# robotarium-1.net
KiCad netlist of a schematic drawn in EAGLE
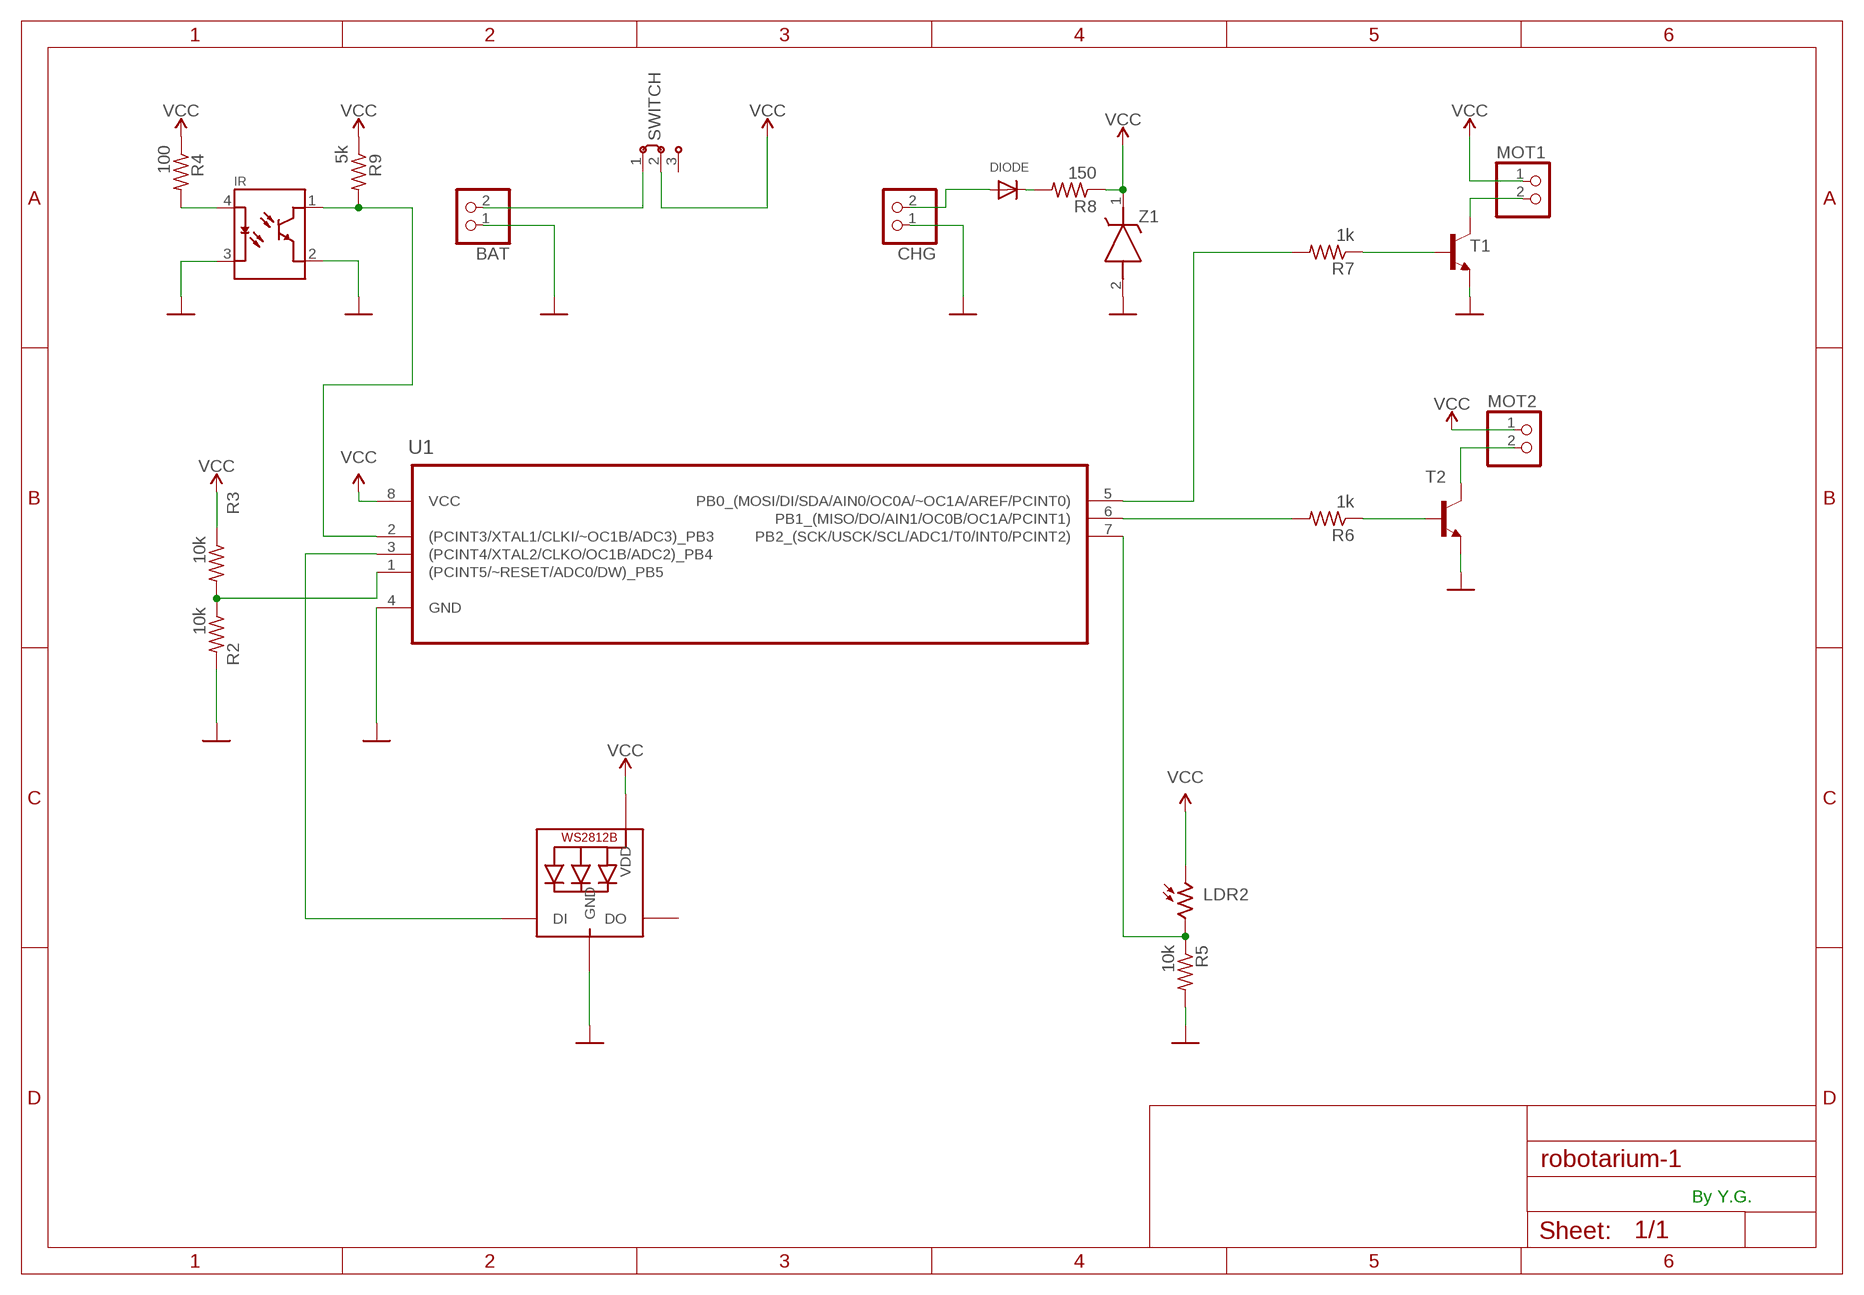
[diagram p0: schematic, sheet 1]

(export (version "E")
  (design (tool "Eeschema 10.0.6"))
  (components
    (comp (ref "BAT")
      (value "PINHD-1X2")
      (footprint "eagle-import:1X02")
      (libsource (lib "eagle-import") (part "PINHD-1X2"))
    )
    (comp (ref "CHG")
      (value "PINHD-1X2")
      (footprint "eagle-import:1X02")
      (libsource (lib "eagle-import") (part "PINHD-1X2"))
    )
    (comp (ref "DIODE")
      (value "DIODEDO-1N4148")
      (footprint "eagle-import:DO-1N4148")
      (libsource (lib "eagle-import") (part "DIODEDO-1N4148"))
    )
    (comp (ref "IR")
      (value "TCRT5000L")
      (footprint "eagle-import:XDCR_TCRT5000L")
      (fields (field (name "MF") "Vishay"))
      (libsource (lib "eagle-import") (part "TCRT5000L"))
    )
    (comp (ref "LDR2")
      (value "A1050_14")
      (footprint "eagle-import:T0-46-A10XX")
      (libsource (lib "eagle-import") (part "A1050_14"))
    )
    (comp (ref "LED2")
      (value "WS2812B5050")
      (footprint "eagle-import:WS2812B")
      (fields (field (name "MF") "SparkFun Electronics") (field (name "MP") "WS2812B"))
      (libsource (lib "eagle-import") (part "WS2812B5050"))
    )
    (comp (ref "MOT1")
      (value "PINHD-1X2")
      (footprint "eagle-import:1X02")
      (libsource (lib "eagle-import") (part "PINHD-1X2"))
    )
    (comp (ref "MOT2")
      (value "PINHD-1X2")
      (footprint "eagle-import:1X02")
      (libsource (lib "eagle-import") (part "PINHD-1X2"))
    )
    (comp (ref "R2")
      (value "10k")
      (footprint "eagle-import:0207_10")
      (libsource (lib "eagle-import") (part "R-US_0207/10"))
    )
    (comp (ref "R3")
      (value "10k")
      (footprint "eagle-import:0207_10")
      (libsource (lib "eagle-import") (part "R-US_0207/10"))
    )
    (comp (ref "R4")
      (value "100")
      (footprint "eagle-import:0207_10")
      (libsource (lib "eagle-import") (part "R-US_0207/10"))
    )
    (comp (ref "R5")
      (value "10k")
      (footprint "eagle-import:0207_10")
      (libsource (lib "eagle-import") (part "R-US_0207/10"))
    )
    (comp (ref "R6")
      (value "1k")
      (footprint "eagle-import:0207_10")
      (libsource (lib "eagle-import") (part "R-US_0207/10"))
    )
    (comp (ref "R7")
      (value "1k")
      (footprint "eagle-import:0207_10")
      (libsource (lib "eagle-import") (part "R-US_0207/10"))
    )
    (comp (ref "R8")
      (value "150")
      (footprint "eagle-import:0207_10")
      (libsource (lib "eagle-import") (part "R-US_0207/10"))
    )
    (comp (ref "R9")
      (value "5k")
      (footprint "eagle-import:0207_10")
      (libsource (lib "eagle-import") (part "R-US_0207/10"))
    )
    (comp (ref "SWITCH")
      (value "J2X2MM")
      (footprint "eagle-import:04C")
      (libsource (lib "eagle-import") (part "J2X2MM"))
    )
    (comp (ref "T1")
      (value "2N3904")
      (footprint "eagle-import:TO92")
      (libsource (lib "eagle-import") (part "2N3904"))
    )
    (comp (ref "T2")
      (value "2N3904")
      (footprint "eagle-import:TO92")
      (libsource (lib "eagle-import") (part "2N3904"))
    )
    (comp (ref "U1")
      (value "ATTINY85-20PU")
      (footprint "eagle-import:DIP254P762X533-8")
      (fields (field (name "MF") "Microchip"))
      (libsource (lib "eagle-import") (part "ATTINY85-20PU"))
    )
    (comp (ref "Z1")
      (value "BZX55C10")
      (footprint "eagle-import:DIOAD950W60L350D150")
      (fields
        (field (name "DIGI-KEY_PART_NUMBER") "BZX55C10-GICT-ND")
        (field (name "MF") "Vishay Semiconductor")
        (field (name "MP") "BZX55C10-TR")
      )
      (libsource (lib "eagle-import") (part "BZX55C10"))
    )
  )
  (nets
    (net (code "1") (name "GND") (class "Default")
      (node (ref "BAT") (pin "1") (pinfunction "1_1") (pintype "passive"))
      (node (ref "CHG") (pin "1") (pinfunction "1_1") (pintype "passive"))
      (node (ref "IR") (pin "2") (pinfunction "E_2") (pintype "passive"))
      (node (ref "IR") (pin "3") (pinfunction "C_3") (pintype "passive"))
      (node (ref "LED2") (pin "3-GND") (pinfunction "GND_3-GND") (pintype "power_in"))
      (node (ref "R2") (pin "2") (pinfunction "2_2") (pintype "passive"))
      (node (ref "R5") (pin "2") (pinfunction "2_2") (pintype "passive"))
      (node (ref "T1") (pin "3") (pinfunction "E_3") (pintype "passive"))
      (node (ref "T2") (pin "3") (pinfunction "E_3") (pintype "passive"))
      (node (ref "U1") (pin "4") (pinfunction "GND_4") (pintype "passive"))
      (node (ref "Z1") (pin "2") (pinfunction "A_2") (pintype "bidirectional"))
    )
    (net (code "2") (name "Net-(BAT-Pad2)") (class "Default")
      (node (ref "BAT") (pin "2") (pinfunction "2_2") (pintype "passive"))
      (node (ref "SWITCH") (pin "1") (pinfunction "1_1") (pintype "passive"))
    )
    (net (code "3") (name "Net-(CHG-Pad2)") (class "Default")
      (node (ref "CHG") (pin "2") (pinfunction "2_2") (pintype "passive"))
      (node (ref "DIODE") (pin "A") (pinfunction "A_A") (pintype "passive"))
    )
    (net (code "4") (name "Net-(DIODE-PadC)") (class "Default")
      (node (ref "DIODE") (pin "C") (pinfunction "C_C") (pintype "passive"))
      (node (ref "R8") (pin "2") (pinfunction "2_2") (pintype "passive"))
    )
    (net (code "5") (name "Net-(IR-A)") (class "Default")
      (node (ref "IR") (pin "4") (pinfunction "A_4") (pintype "passive"))
      (node (ref "R4") (pin "2") (pinfunction "2_2") (pintype "passive"))
    )
    (net (code "6") (name "Net-(IR-CO)") (class "Default")
      (node (ref "IR") (pin "1") (pinfunction "CO_1") (pintype "passive"))
      (node (ref "R9") (pin "2") (pinfunction "2_2") (pintype "passive"))
      (node (ref "U1") (pin "2") (pinfunction "(PCINT3/XTAL1/CLKI/~{OC1B/ADC3})_PB3_2") (pintype "bidirectional"))
    )
    (net (code "7") (name "Net-(LED2-DI)") (class "Default")
      (node (ref "LED2") (pin "4-DIN") (pinfunction "DI_4-DIN") (pintype "input"))
      (node (ref "U1") (pin "3") (pinfunction "(PCINT4/XTAL2/CLKO/OC1B/ADC2)_PB4_3") (pintype "bidirectional"))
    )
    (net (code "8") (name "Net-(T1-B)") (class "Default")
      (node (ref "R7") (pin "1") (pinfunction "1_1") (pintype "passive"))
      (node (ref "T1") (pin "2") (pinfunction "B_2") (pintype "passive"))
    )
    (net (code "9") (name "Net-(T1-C)") (class "Default")
      (node (ref "MOT1") (pin "2") (pinfunction "2_2") (pintype "passive"))
      (node (ref "T1") (pin "1") (pinfunction "C_1") (pintype "passive"))
    )
    (net (code "10") (name "Net-(T2-B)") (class "Default")
      (node (ref "R6") (pin "1") (pinfunction "1_1") (pintype "passive"))
      (node (ref "T2") (pin "2") (pinfunction "B_2") (pintype "passive"))
    )
    (net (code "11") (name "Net-(T2-C)") (class "Default")
      (node (ref "MOT2") (pin "2") (pinfunction "2_2") (pintype "passive"))
      (node (ref "T2") (pin "1") (pinfunction "C_1") (pintype "passive"))
    )
    (net (code "12") (name "Net-(U1-(PCINT5{slash}~{RESET{slash}ADC0{slash}DW})_PB5)") (class "Default")
      (node (ref "R2") (pin "1") (pinfunction "1_1") (pintype "passive"))
      (node (ref "R3") (pin "2") (pinfunction "2_2") (pintype "passive"))
      (node (ref "U1") (pin "1") (pinfunction "(PCINT5/~{RESET/ADC0/DW})_PB5_1") (pintype "bidirectional"))
    )
    (net (code "13") (name "Net-(U1-PB0_(MOSI{slash}DI{slash}SDA{slash}AIN0{slash}OC0A{slash}~{OC1A{slash}AREF{slash}PCINT0}))") (class "Default")
      (node (ref "R7") (pin "2") (pinfunction "2_2") (pintype "passive"))
      (node (ref "U1") (pin "5") (pinfunction "PB0_(MOSI/DI/SDA/AIN0/OC0A/~{OC1A/AREF/PCINT0})_5") (pintype "bidirectional"))
    )
    (net (code "14") (name "Net-(U1-PB1_(MISO{slash}DO{slash}AIN1{slash}OC0B{slash}OC1A{slash}PCINT1))") (class "Default")
      (node (ref "R6") (pin "2") (pinfunction "2_2") (pintype "passive"))
      (node (ref "U1") (pin "6") (pinfunction "PB1_(MISO/DO/AIN1/OC0B/OC1A/PCINT1)_6") (pintype "bidirectional"))
    )
    (net (code "15") (name "Net-(U1-PB2_(SCK{slash}USCK{slash}SCL{slash}ADC1{slash}T0{slash}INT0{slash}PCINT2))") (class "Default")
      (node (ref "LDR2") (pin "2") (pinfunction "2_2") (pintype "passive"))
      (node (ref "R5") (pin "1") (pinfunction "1_1") (pintype "passive"))
      (node (ref "U1") (pin "7") (pinfunction "PB2_(SCK/USCK/SCL/ADC1/T0/INT0/PCINT2)_7") (pintype "bidirectional"))
    )
    (net (code "16") (name "VCC") (class "Default")
      (node (ref "LDR2") (pin "1") (pinfunction "1_1") (pintype "passive"))
      (node (ref "LED2") (pin "1-VDD") (pinfunction "VDD_1-VDD") (pintype "power_in"))
      (node (ref "MOT1") (pin "1") (pinfunction "1_1") (pintype "passive"))
      (node (ref "MOT2") (pin "1") (pinfunction "1_1") (pintype "passive"))
      (node (ref "R3") (pin "1") (pinfunction "1_1") (pintype "passive"))
      (node (ref "R4") (pin "1") (pinfunction "1_1") (pintype "passive"))
      (node (ref "R8") (pin "1") (pinfunction "1_1") (pintype "passive"))
      (node (ref "R9") (pin "1") (pinfunction "1_1") (pintype "passive"))
      (node (ref "SWITCH") (pin "2") (pinfunction "2_2") (pintype "passive"))
      (node (ref "U1") (pin "8") (pinfunction "VCC_8") (pintype "power_in"))
      (node (ref "Z1") (pin "1") (pinfunction "K_1") (pintype "bidirectional"))
    )
    (net (code "17") (name "unconnected-(LED2-DO-Pad2-DOUT)") (class "Default")
      (node (ref "LED2") (pin "2-DOUT") (pinfunction "DO_2-DOUT") (pintype "output"))
    )
    (net (code "18") (name "unconnected-(SWITCH-Pad3)") (class "Default")
      (node (ref "SWITCH") (pin "3") (pinfunction "3_3") (pintype "passive"))
    )
  )
)
